# sch_shield.net
KiCad netlist of a schematic drawn in EAGLE
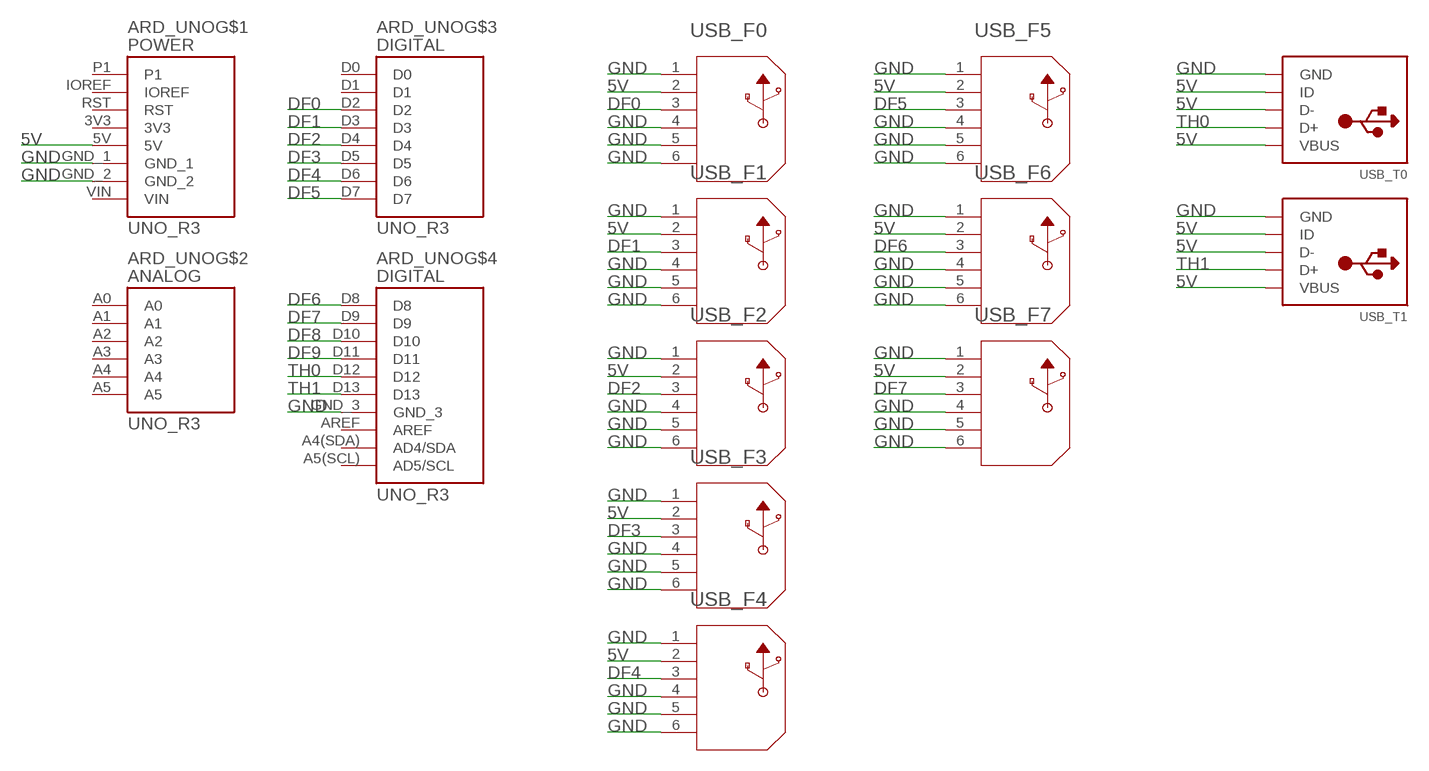
[diagram p0: schematic, sheet 1]

(export (version "E")
  (design (tool "Eeschema 10.0.6"))
  (components
    (comp (ref "ARD_UNO")
      (value "UNO_R3")
      (footprint "eagle-import:ARDUINO_UNO_R3")
      (fields (field (name "MF") "Arduino") (field (name "MP") "UNO R3"))
      (libsource (lib "eagle-import") (part "UNO_R3"))
    )
    (comp (ref "USB_F0")
      (value "292303-3")
      (footprint "eagle-import:CONN4_292303_TEC")
      (fields (field (name "COPYRIGHT") "Copyright (C) 2016 Accelerated Designs. All rights reserved"))
      (libsource (lib "eagle-import") (part "292303-3"))
    )
    (comp (ref "USB_F1")
      (value "292303-3")
      (footprint "eagle-import:CONN4_292303_TEC")
      (fields (field (name "COPYRIGHT") "Copyright (C) 2016 Accelerated Designs. All rights reserved"))
      (libsource (lib "eagle-import") (part "292303-3"))
    )
    (comp (ref "USB_F2")
      (value "292303-3")
      (footprint "eagle-import:CONN4_292303_TEC")
      (fields (field (name "COPYRIGHT") "Copyright (C) 2016 Accelerated Designs. All rights reserved"))
      (libsource (lib "eagle-import") (part "292303-3"))
    )
    (comp (ref "USB_F3")
      (value "292303-3")
      (footprint "eagle-import:CONN4_292303_TEC")
      (fields (field (name "COPYRIGHT") "Copyright (C) 2016 Accelerated Designs. All rights reserved"))
      (libsource (lib "eagle-import") (part "292303-3"))
    )
    (comp (ref "USB_F4")
      (value "292303-3")
      (footprint "eagle-import:CONN4_292303_TEC")
      (fields (field (name "COPYRIGHT") "Copyright (C) 2016 Accelerated Designs. All rights reserved"))
      (libsource (lib "eagle-import") (part "292303-3"))
    )
    (comp (ref "USB_F5")
      (value "292303-3")
      (footprint "eagle-import:CONN4_292303_TEC")
      (fields (field (name "COPYRIGHT") "Copyright (C) 2016 Accelerated Designs. All rights reserved"))
      (libsource (lib "eagle-import") (part "292303-3"))
    )
    (comp (ref "USB_F6")
      (value "292303-3")
      (footprint "eagle-import:CONN4_292303_TEC")
      (fields (field (name "COPYRIGHT") "Copyright (C) 2016 Accelerated Designs. All rights reserved"))
      (libsource (lib "eagle-import") (part "292303-3"))
    )
    (comp (ref "USB_F7")
      (value "292303-3")
      (footprint "eagle-import:CONN4_292303_TEC")
      (fields (field (name "COPYRIGHT") "Copyright (C) 2016 Accelerated Designs. All rights reserved"))
      (libsource (lib "eagle-import") (part "292303-3"))
    )
    (comp (ref "USB_T0")
      (value "USBTHM")
      (footprint "eagle-import:USB-MINIB-THM")
      (libsource (lib "eagle-import") (part "USBTHM"))
    )
    (comp (ref "USB_T1")
      (value "USBTHM")
      (footprint "eagle-import:USB-MINIB-THM")
      (libsource (lib "eagle-import") (part "USBTHM"))
    )
  )
  (nets
    (net (code "1") (name "/3V3") (class "Default")
      (node (ref "ARD_UNO") (pin "3V3") (pinfunction "3V3_3V3") (pintype "power_in"))
    )
    (net (code "2") (name "/5V") (class "Default")
      (node (ref "ARD_UNO") (pin "5V") (pinfunction "5V_5V") (pintype "power_in"))
      (node (ref "USB_F0") (pin "2") (pinfunction "2_2") (pintype "passive"))
      (node (ref "USB_F1") (pin "2") (pinfunction "2_2") (pintype "passive"))
      (node (ref "USB_F2") (pin "2") (pinfunction "2_2") (pintype "passive"))
      (node (ref "USB_F3") (pin "2") (pinfunction "2_2") (pintype "passive"))
      (node (ref "USB_F4") (pin "2") (pinfunction "2_2") (pintype "passive"))
      (node (ref "USB_F5") (pin "2") (pinfunction "2_2") (pintype "passive"))
      (node (ref "USB_F6") (pin "2") (pinfunction "2_2") (pintype "passive"))
      (node (ref "USB_F7") (pin "2") (pinfunction "2_2") (pintype "passive"))
      (node (ref "USB_T0") (pin "D-") (pinfunction "D-_D-") (pintype "bidirectional"))
      (node (ref "USB_T0") (pin "ID") (pinfunction "ID_ID") (pintype "bidirectional"))
      (node (ref "USB_T0") (pin "VBUS") (pinfunction "VBUS_VBUS") (pintype "power_in"))
      (node (ref "USB_T1") (pin "D-") (pinfunction "D-_D-") (pintype "bidirectional"))
      (node (ref "USB_T1") (pin "ID") (pinfunction "ID_ID") (pintype "bidirectional"))
      (node (ref "USB_T1") (pin "VBUS") (pinfunction "VBUS_VBUS") (pintype "power_in"))
    )
    (net (code "3") (name "/DF0") (class "Default")
      (node (ref "ARD_UNO") (pin "D2") (pinfunction "D2_D2") (pintype "bidirectional"))
      (node (ref "USB_F0") (pin "3") (pinfunction "3_3") (pintype "passive"))
    )
    (net (code "4") (name "/DF1") (class "Default")
      (node (ref "ARD_UNO") (pin "D3") (pinfunction "D3_D3") (pintype "bidirectional"))
      (node (ref "USB_F1") (pin "3") (pinfunction "3_3") (pintype "passive"))
    )
    (net (code "5") (name "/DF2") (class "Default")
      (node (ref "ARD_UNO") (pin "D4") (pinfunction "D4_D4") (pintype "bidirectional"))
      (node (ref "USB_F2") (pin "3") (pinfunction "3_3") (pintype "passive"))
    )
    (net (code "6") (name "/DF3") (class "Default")
      (node (ref "ARD_UNO") (pin "D5") (pinfunction "D5_D5") (pintype "bidirectional"))
      (node (ref "USB_F3") (pin "3") (pinfunction "3_3") (pintype "passive"))
    )
    (net (code "7") (name "/DF4") (class "Default")
      (node (ref "ARD_UNO") (pin "D6") (pinfunction "D6_D6") (pintype "bidirectional"))
      (node (ref "USB_F4") (pin "3") (pinfunction "3_3") (pintype "passive"))
    )
    (net (code "8") (name "/DF5") (class "Default")
      (node (ref "ARD_UNO") (pin "D7") (pinfunction "D7_D7") (pintype "bidirectional"))
      (node (ref "USB_F5") (pin "3") (pinfunction "3_3") (pintype "passive"))
    )
    (net (code "9") (name "/DF6") (class "Default")
      (node (ref "ARD_UNO") (pin "D8") (pinfunction "D8_D8") (pintype "bidirectional"))
      (node (ref "USB_F6") (pin "3") (pinfunction "3_3") (pintype "passive"))
    )
    (net (code "10") (name "/DF7") (class "Default")
      (node (ref "ARD_UNO") (pin "D9") (pinfunction "D9_D9") (pintype "bidirectional"))
      (node (ref "USB_F7") (pin "3") (pinfunction "3_3") (pintype "passive"))
    )
    (net (code "11") (name "/DF8") (class "Default")
      (node (ref "ARD_UNO") (pin "D10") (pinfunction "D10_D10") (pintype "bidirectional"))
    )
    (net (code "12") (name "/DF9") (class "Default")
      (node (ref "ARD_UNO") (pin "D11") (pinfunction "D11_D11") (pintype "bidirectional"))
    )
    (net (code "13") (name "/GND") (class "Default")
      (node (ref "ARD_UNO") (pin "GND_1") (pinfunction "GND_1_GND_1") (pintype "power_in"))
      (node (ref "ARD_UNO") (pin "GND_2") (pinfunction "GND_2_GND_2") (pintype "power_in"))
      (node (ref "ARD_UNO") (pin "GND_3") (pinfunction "GND_3_GND_3") (pintype "power_in"))
      (node (ref "USB_F0") (pin "1") (pinfunction "1_1") (pintype "passive"))
      (node (ref "USB_F0") (pin "4") (pinfunction "4_4") (pintype "passive"))
      (node (ref "USB_F0") (pin "5") (pinfunction "5_5") (pintype "passive"))
      (node (ref "USB_F0") (pin "6") (pinfunction "6_6") (pintype "passive"))
      (node (ref "USB_F1") (pin "1") (pinfunction "1_1") (pintype "passive"))
      (node (ref "USB_F1") (pin "4") (pinfunction "4_4") (pintype "passive"))
      (node (ref "USB_F1") (pin "5") (pinfunction "5_5") (pintype "passive"))
      (node (ref "USB_F1") (pin "6") (pinfunction "6_6") (pintype "passive"))
      (node (ref "USB_F2") (pin "1") (pinfunction "1_1") (pintype "passive"))
      (node (ref "USB_F2") (pin "4") (pinfunction "4_4") (pintype "passive"))
      (node (ref "USB_F2") (pin "5") (pinfunction "5_5") (pintype "passive"))
      (node (ref "USB_F2") (pin "6") (pinfunction "6_6") (pintype "passive"))
      (node (ref "USB_F3") (pin "1") (pinfunction "1_1") (pintype "passive"))
      (node (ref "USB_F3") (pin "4") (pinfunction "4_4") (pintype "passive"))
      (node (ref "USB_F3") (pin "5") (pinfunction "5_5") (pintype "passive"))
      (node (ref "USB_F3") (pin "6") (pinfunction "6_6") (pintype "passive"))
      (node (ref "USB_F4") (pin "1") (pinfunction "1_1") (pintype "passive"))
      (node (ref "USB_F4") (pin "4") (pinfunction "4_4") (pintype "passive"))
      (node (ref "USB_F4") (pin "5") (pinfunction "5_5") (pintype "passive"))
      (node (ref "USB_F4") (pin "6") (pinfunction "6_6") (pintype "passive"))
      (node (ref "USB_F5") (pin "1") (pinfunction "1_1") (pintype "passive"))
      (node (ref "USB_F5") (pin "4") (pinfunction "4_4") (pintype "passive"))
      (node (ref "USB_F5") (pin "5") (pinfunction "5_5") (pintype "passive"))
      (node (ref "USB_F5") (pin "6") (pinfunction "6_6") (pintype "passive"))
      (node (ref "USB_F6") (pin "1") (pinfunction "1_1") (pintype "passive"))
      (node (ref "USB_F6") (pin "4") (pinfunction "4_4") (pintype "passive"))
      (node (ref "USB_F6") (pin "5") (pinfunction "5_5") (pintype "passive"))
      (node (ref "USB_F6") (pin "6") (pinfunction "6_6") (pintype "passive"))
      (node (ref "USB_F7") (pin "1") (pinfunction "1_1") (pintype "passive"))
      (node (ref "USB_F7") (pin "4") (pinfunction "4_4") (pintype "passive"))
      (node (ref "USB_F7") (pin "5") (pinfunction "5_5") (pintype "passive"))
      (node (ref "USB_F7") (pin "6") (pinfunction "6_6") (pintype "passive"))
      (node (ref "USB_T0") (pin "GND") (pinfunction "GND_GND") (pintype "power_in"))
      (node (ref "USB_T1") (pin "GND") (pinfunction "GND_GND") (pintype "power_in"))
    )
    (net (code "14") (name "/TH0") (class "Default")
      (node (ref "ARD_UNO") (pin "D12") (pinfunction "D12_D12") (pintype "bidirectional"))
      (node (ref "USB_T0") (pin "D+") (pinfunction "D+_D+") (pintype "bidirectional"))
    )
    (net (code "15") (name "/TH1") (class "Default")
      (node (ref "ARD_UNO") (pin "D13") (pinfunction "D13_D13") (pintype "bidirectional"))
      (node (ref "USB_T1") (pin "D+") (pinfunction "D+_D+") (pintype "bidirectional"))
    )
    (net (code "16") (name "/VIN") (class "Default")
      (node (ref "ARD_UNO") (pin "VIN") (pinfunction "VIN_VIN") (pintype "power_in"))
    )
    (net (code "17") (name "unconnected-(ARD_UNO-PadA0)") (class "Default")
      (node (ref "ARD_UNO") (pin "A0") (pinfunction "A0_A0") (pintype "bidirectional"))
    )
    (net (code "18") (name "unconnected-(ARD_UNO-PadA1)") (class "Default")
      (node (ref "ARD_UNO") (pin "A1") (pinfunction "A1_A1") (pintype "bidirectional"))
    )
    (net (code "19") (name "unconnected-(ARD_UNO-PadA2)") (class "Default")
      (node (ref "ARD_UNO") (pin "A2") (pinfunction "A2_A2") (pintype "bidirectional"))
    )
    (net (code "20") (name "unconnected-(ARD_UNO-PadA3)") (class "Default")
      (node (ref "ARD_UNO") (pin "A3") (pinfunction "A3_A3") (pintype "bidirectional"))
    )
    (net (code "21") (name "unconnected-(ARD_UNO-PadA4)") (class "Default")
      (node (ref "ARD_UNO") (pin "A4") (pinfunction "A4_A4") (pintype "bidirectional"))
    )
    (net (code "22") (name "unconnected-(ARD_UNO-PadA5)") (class "Default")
      (node (ref "ARD_UNO") (pin "A5") (pinfunction "A5_A5") (pintype "bidirectional"))
    )
    (net (code "23") (name "unconnected-(ARD_UNO-PadAREF)") (class "Default")
      (node (ref "ARD_UNO") (pin "AREF") (pinfunction "AREF_AREF") (pintype "bidirectional"))
    )
    (net (code "24") (name "unconnected-(ARD_UNO-PadD0)") (class "Default")
      (node (ref "ARD_UNO") (pin "D0") (pinfunction "D0_D0") (pintype "bidirectional"))
    )
    (net (code "25") (name "unconnected-(ARD_UNO-PadD1)") (class "Default")
      (node (ref "ARD_UNO") (pin "D1") (pinfunction "D1_D1") (pintype "bidirectional"))
    )
    (net (code "26") (name "unconnected-(ARD_UNO-PadIOREF)") (class "Default")
      (node (ref "ARD_UNO") (pin "IOREF") (pinfunction "IOREF_IOREF") (pintype "bidirectional"))
    )
    (net (code "27") (name "unconnected-(ARD_UNO-PadP1)") (class "Default")
      (node (ref "ARD_UNO") (pin "P1") (pinfunction "P1_P1") (pintype "bidirectional"))
    )
    (net (code "28") (name "unconnected-(ARD_UNO-PadRST)") (class "Default")
      (node (ref "ARD_UNO") (pin "RST") (pinfunction "RST_RST") (pintype "bidirectional"))
    )
    (net (code "29") (name "unconnected-(ARD_UNOD-AD4{slash}SDA-PadA4(SDA))") (class "Default")
      (node (ref "ARD_UNO") (pin "A4(SDA)") (pinfunction "AD4/SDA_A4(SDA)") (pintype "bidirectional"))
    )
    (net (code "30") (name "unconnected-(ARD_UNOD-AD5{slash}SCL-PadA5(SCL))") (class "Default")
      (node (ref "ARD_UNO") (pin "A5(SCL)") (pinfunction "AD5/SCL_A5(SCL)") (pintype "bidirectional"))
    )
  )
)
